# Gas.net
KiCad netlist of a schematic drawn in EAGLE
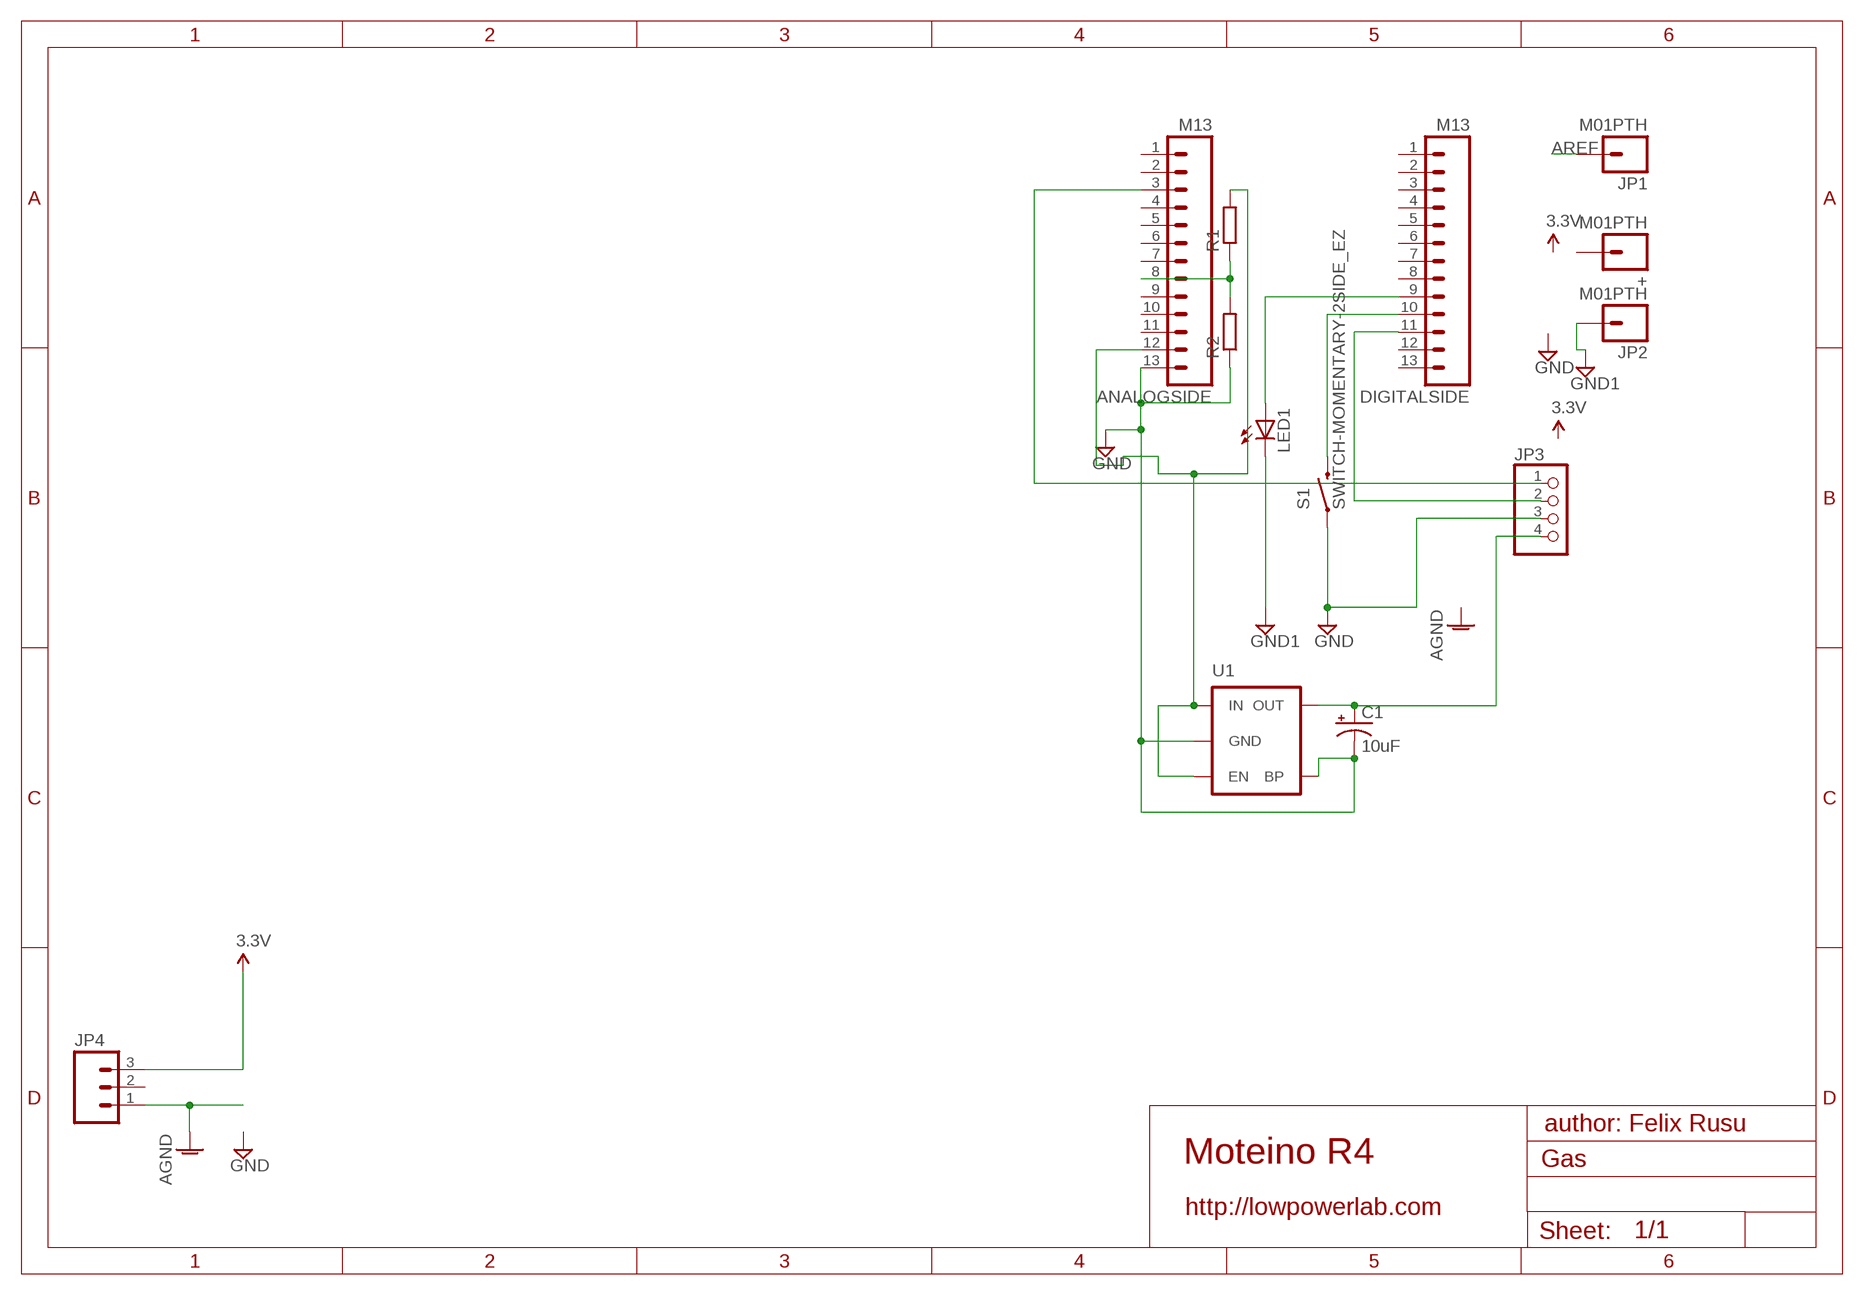
[diagram p0: schematic, sheet 1]

(export (version "E")
  (design (tool "Eeschema 10.0.6"))
  (components
    (comp (ref "+")
      (value "M01PTH")
      (footprint "eagle-import:1X01")
      (libsource (lib "eagle-import") (part "M01PTH"))
    )
    (comp (ref "ANALOGSIDE")
      (value "M13")
      (footprint "eagle-import:1X13")
      (libsource (lib "eagle-import") (part "M13"))
    )
    (comp (ref "C1")
      (value "10uF")
      (footprint "eagle-import:EIA3216")
      (libsource (lib "eagle-import") (part "10UF-16V-10%(TANT)"))
    )
    (comp (ref "DIGITALSIDE")
      (value "M13")
      (footprint "eagle-import:1X13")
      (libsource (lib "eagle-import") (part "M13"))
    )
    (comp (ref "JP1")
      (value "M01PTH")
      (footprint "eagle-import:1X01")
      (libsource (lib "eagle-import") (part "M01PTH"))
    )
    (comp (ref "JP2")
      (value "M01PTH")
      (footprint "eagle-import:1X01")
      (libsource (lib "eagle-import") (part "M01PTH"))
    )
    (comp (ref "JP3")
      (value "PINHD-1X4")
      (footprint "eagle-import:1X04")
      (libsource (lib "eagle-import") (part "PINHD-1X4"))
    )
    (comp (ref "JP4")
      (value "M03PTH")
      (footprint "eagle-import:1X03")
      (libsource (lib "eagle-import") (part "M03PTH"))
    )
    (comp (ref "LED1")
      (value "LED3MM")
      (footprint "eagle-import:LED3MM")
      (libsource (lib "eagle-import") (part "LED3MM"))
    )
    (comp (ref "R1")
      (value "R-EU_0204/7")
      (footprint "eagle-import:0204_7")
      (libsource (lib "eagle-import") (part "R-EU_0204/7"))
    )
    (comp (ref "R2")
      (value "R-EU_0204/7")
      (footprint "eagle-import:0204_7")
      (libsource (lib "eagle-import") (part "R-EU_0204/7"))
    )
    (comp (ref "S1")
      (value "SWITCH-MOMENTARY-2SIDE_EZ")
      (footprint "eagle-import:TACTILE-PTH-SIDEEZ")
      (libsource (lib "eagle-import") (part "SWITCH-MOMENTARY-2SIDE_EZ"))
    )
    (comp (ref "U1")
      (value "MIC52055V")
      (footprint "eagle-import:SOT23-5")
      (libsource (lib "eagle-import") (part "MIC52055V"))
    )
  )
  (nets
    (net (code "1") (name "/AREF") (class "Default")
      (node (ref "JP1") (pin "1") (pinfunction "1_1") (pintype "passive"))
    )
    (net (code "2") (name "3.3V") (class "Default")
      (node (ref "JP4") (pin "3") (pinfunction "3_3") (pintype "passive"))
    )
    (net (code "3") (name "AGND") (class "Default")
      (node (ref "JP4") (pin "1") (pinfunction "1_1") (pintype "passive"))
    )
    (net (code "4") (name "GND") (class "Default")
      (node (ref "ANALOGSIDE") (pin "13") (pinfunction "13_13") (pintype "passive"))
      (node (ref "C1") (pin "C") (pinfunction "-_C") (pintype "passive"))
      (node (ref "JP3") (pin "3") (pinfunction "3_3") (pintype "passive"))
      (node (ref "R2") (pin "1") (pinfunction "1_1") (pintype "passive"))
      (node (ref "S1") (pin "1") (pinfunction "1_1") (pintype "passive"))
      (node (ref "U1") (pin "2") (pinfunction "GND_2") (pintype "input"))
      (node (ref "U1") (pin "4") (pinfunction "BP_4") (pintype "input"))
    )
    (net (code "5") (name "GND1") (class "Default")
      (node (ref "JP2") (pin "1") (pinfunction "1_1") (pintype "passive"))
      (node (ref "LED1") (pin "K") (pinfunction "C_K") (pintype "passive"))
    )
    (net (code "6") (name "Net-(ANALOGSIDE-Pad3)") (class "Default")
      (node (ref "ANALOGSIDE") (pin "3") (pinfunction "3_3") (pintype "passive"))
      (node (ref "JP3") (pin "1") (pinfunction "1_1") (pintype "passive"))
    )
    (net (code "7") (name "Net-(ANALOGSIDE-Pad8)") (class "Default")
      (node (ref "ANALOGSIDE") (pin "8") (pinfunction "8_8") (pintype "passive"))
      (node (ref "R1") (pin "1") (pinfunction "1_1") (pintype "passive"))
      (node (ref "R2") (pin "2") (pinfunction "2_2") (pintype "passive"))
    )
    (net (code "8") (name "Net-(C1-+)") (class "Default")
      (node (ref "C1") (pin "A") (pinfunction "+_A") (pintype "passive"))
      (node (ref "JP3") (pin "4") (pinfunction "4_4") (pintype "passive"))
      (node (ref "U1") (pin "5") (pinfunction "OUT_5") (pintype "passive"))
    )
    (net (code "9") (name "Net-(DIGITALSIDE-Pad9)") (class "Default")
      (node (ref "DIGITALSIDE") (pin "9") (pinfunction "9_9") (pintype "passive"))
      (node (ref "LED1") (pin "A") (pinfunction "A_A") (pintype "passive"))
    )
    (net (code "10") (name "Net-(DIGITALSIDE-Pad10)") (class "Default")
      (node (ref "DIGITALSIDE") (pin "10") (pinfunction "10_10") (pintype "passive"))
      (node (ref "S1") (pin "2") (pinfunction "2_2") (pintype "passive"))
    )
    (net (code "11") (name "Net-(DIGITALSIDE-Pad11)") (class "Default")
      (node (ref "DIGITALSIDE") (pin "11") (pinfunction "11_11") (pintype "passive"))
      (node (ref "JP3") (pin "2") (pinfunction "2_2") (pintype "passive"))
    )
    (net (code "12") (name "Net-(U1-EN)") (class "Default")
      (node (ref "ANALOGSIDE") (pin "12") (pinfunction "12_12") (pintype "passive"))
      (node (ref "R1") (pin "2") (pinfunction "2_2") (pintype "passive"))
      (node (ref "U1") (pin "1") (pinfunction "IN_1") (pintype "input"))
      (node (ref "U1") (pin "3") (pinfunction "EN_3") (pintype "input"))
    )
    (net (code "13") (name "unconnected-(+-Pad1)") (class "Default")
      (node (ref "+") (pin "1") (pinfunction "1_1") (pintype "passive"))
    )
    (net (code "14") (name "unconnected-(ANALOGSIDE-Pad1)") (class "Default")
      (node (ref "ANALOGSIDE") (pin "1") (pinfunction "1_1") (pintype "passive"))
    )
    (net (code "15") (name "unconnected-(ANALOGSIDE-Pad2)") (class "Default")
      (node (ref "ANALOGSIDE") (pin "2") (pinfunction "2_2") (pintype "passive"))
    )
    (net (code "16") (name "unconnected-(ANALOGSIDE-Pad4)") (class "Default")
      (node (ref "ANALOGSIDE") (pin "4") (pinfunction "4_4") (pintype "passive"))
    )
    (net (code "17") (name "unconnected-(ANALOGSIDE-Pad5)") (class "Default")
      (node (ref "ANALOGSIDE") (pin "5") (pinfunction "5_5") (pintype "passive"))
    )
    (net (code "18") (name "unconnected-(ANALOGSIDE-Pad6)") (class "Default")
      (node (ref "ANALOGSIDE") (pin "6") (pinfunction "6_6") (pintype "passive"))
    )
    (net (code "19") (name "unconnected-(ANALOGSIDE-Pad7)") (class "Default")
      (node (ref "ANALOGSIDE") (pin "7") (pinfunction "7_7") (pintype "passive"))
    )
    (net (code "20") (name "unconnected-(ANALOGSIDE-Pad9)") (class "Default")
      (node (ref "ANALOGSIDE") (pin "9") (pinfunction "9_9") (pintype "passive"))
    )
    (net (code "21") (name "unconnected-(ANALOGSIDE-Pad10)") (class "Default")
      (node (ref "ANALOGSIDE") (pin "10") (pinfunction "10_10") (pintype "passive"))
    )
    (net (code "22") (name "unconnected-(ANALOGSIDE-Pad11)") (class "Default")
      (node (ref "ANALOGSIDE") (pin "11") (pinfunction "11_11") (pintype "passive"))
    )
    (net (code "23") (name "unconnected-(DIGITALSIDE-Pad1)") (class "Default")
      (node (ref "DIGITALSIDE") (pin "1") (pinfunction "1_1") (pintype "passive"))
    )
    (net (code "24") (name "unconnected-(DIGITALSIDE-Pad2)") (class "Default")
      (node (ref "DIGITALSIDE") (pin "2") (pinfunction "2_2") (pintype "passive"))
    )
    (net (code "25") (name "unconnected-(DIGITALSIDE-Pad3)") (class "Default")
      (node (ref "DIGITALSIDE") (pin "3") (pinfunction "3_3") (pintype "passive"))
    )
    (net (code "26") (name "unconnected-(DIGITALSIDE-Pad4)") (class "Default")
      (node (ref "DIGITALSIDE") (pin "4") (pinfunction "4_4") (pintype "passive"))
    )
    (net (code "27") (name "unconnected-(DIGITALSIDE-Pad5)") (class "Default")
      (node (ref "DIGITALSIDE") (pin "5") (pinfunction "5_5") (pintype "passive"))
    )
    (net (code "28") (name "unconnected-(DIGITALSIDE-Pad6)") (class "Default")
      (node (ref "DIGITALSIDE") (pin "6") (pinfunction "6_6") (pintype "passive"))
    )
    (net (code "29") (name "unconnected-(DIGITALSIDE-Pad7)") (class "Default")
      (node (ref "DIGITALSIDE") (pin "7") (pinfunction "7_7") (pintype "passive"))
    )
    (net (code "30") (name "unconnected-(DIGITALSIDE-Pad8)") (class "Default")
      (node (ref "DIGITALSIDE") (pin "8") (pinfunction "8_8") (pintype "passive"))
    )
    (net (code "31") (name "unconnected-(DIGITALSIDE-Pad12)") (class "Default")
      (node (ref "DIGITALSIDE") (pin "12") (pinfunction "12_12") (pintype "passive"))
    )
    (net (code "32") (name "unconnected-(DIGITALSIDE-Pad13)") (class "Default")
      (node (ref "DIGITALSIDE") (pin "13") (pinfunction "13_13") (pintype "passive"))
    )
    (net (code "33") (name "unconnected-(JP4-Pad2)") (class "Default")
      (node (ref "JP4") (pin "2") (pinfunction "2_2") (pintype "passive"))
    )
  )
)
